# CPU.net
KiCad netlist of a schematic drawn in Altium Designer
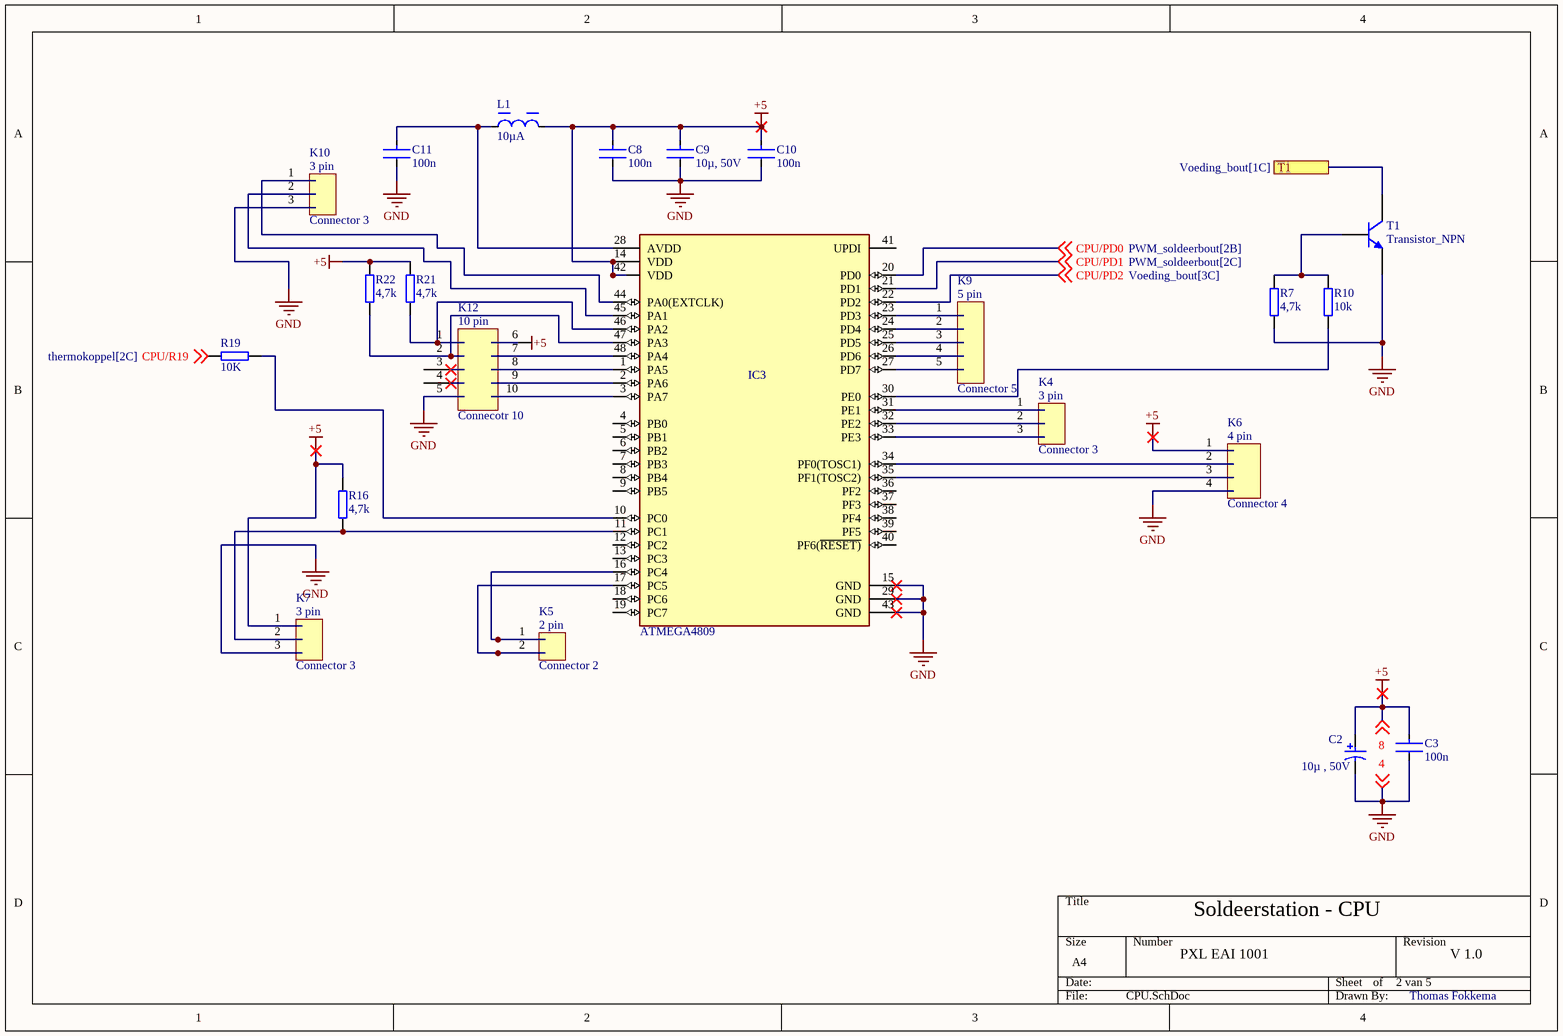
[diagram p0: CPU.SchDoc]

(export (version "E")
  (design (tool "Eeschema 10.0.6"))
  (components
    (comp (ref "C2")
      (value "10µ , 50V")
      (footprint "CE_D8_L10")
      (fields (field (name "MANUFACTURER") "Panasonic"))
      (libsource (lib "Schlib1") (part "Capacitor_Electrolytic"))
    )
    (comp (ref "C3")
      (value "100n")
      (footprint "CC_0805_L")
      (fields
        (field (name "MANUFACTURER") "KEMET")
        (field (name "OCTOPART") "https://octopart.com/c0805c224k5ractu-kemet-144670")
        (field (name "MANUFACTURER PART NUMBER") "C0805C224K5RACTU")
      )
      (libsource (lib "Schlib1") (part "Capacitor_Ceramic"))
    )
    (comp (ref "C8")
      (value "100n")
      (footprint "CC_0805_L")
      (fields
        (field (name "MANUFACTURER") "KEMET")
        (field (name "OCTOPART") "https://octopart.com/c0805c224k5ractu-kemet-144670")
        (field (name "MANUFACTURER PART NUMBER") "C0805C224K5RACTU")
      )
      (libsource (lib "Schlib1") (part "Capacitor_Ceramic"))
    )
    (comp (ref "C9")
      (value "10µ, 50V")
      (footprint "CC_0805_L")
      (fields
        (field (name "MANUFACTURER") "KEMET")
        (field (name "OCTOPART") "https://octopart.com/c0805c224k5ractu-kemet-144670")
        (field (name "MANUFACTURER PART NUMBER") "C0805C224K5RACTU")
      )
      (libsource (lib "Schlib1") (part "Capacitor_Ceramic"))
    )
    (comp (ref "C10")
      (value "100n")
      (footprint "CC_0805_L")
      (fields
        (field (name "MANUFACTURER") "KEMET")
        (field (name "OCTOPART") "https://octopart.com/c0805c224k5ractu-kemet-144670")
        (field (name "MANUFACTURER PART NUMBER") "C0805C224K5RACTU")
      )
      (libsource (lib "Schlib1") (part "Capacitor_Ceramic"))
    )
    (comp (ref "C11")
      (value "100n")
      (footprint "CC_0805_L")
      (fields
        (field (name "MANUFACTURER") "KEMET")
        (field (name "OCTOPART") "https://octopart.com/c0805c224k5ractu-kemet-144670")
        (field (name "MANUFACTURER PART NUMBER") "C0805C224K5RACTU")
      )
      (libsource (lib "Schlib1") (part "Capacitor_Ceramic"))
    )
    (comp (ref "IC3")
      (value "ATMEGA4809")
      (footprint "TQFP_48_M")
      (libsource (lib "Schlib1") (part "ATMEGA4809"))
    )
    (comp (ref "K4")
      (value "Connector 3")
      (footprint "HDR1X3")
      (libsource (lib "Soldeerstation_Final") (part "Connector 3"))
    )
    (comp (ref "K5")
      (value "Connector 2")
      (footprint "HDR1X2")
      (libsource (lib "Soldeerstation_Final") (part "Connector 2"))
    )
    (comp (ref "K6")
      (value "Connector 4")
      (footprint "HDR1X4")
      (libsource (lib "Soldeerstation_Final") (part "Connector 4"))
    )
    (comp (ref "K7")
      (value "Connector 3")
      (footprint "HDR1X3")
      (libsource (lib "Soldeerstation_Final") (part "Connector 3"))
    )
    (comp (ref "K9")
      (value "Connector 5")
      (footprint "HDR1X5")
      (libsource (lib "Soldeerstation_Final") (part "Connector 5"))
    )
    (comp (ref "K10")
      (value "Connector 3")
      (footprint "HDR1X3")
      (libsource (lib "Soldeerstation_Final") (part "Connector 3"))
    )
    (comp (ref "K12")
      (value "Connecotr 10")
      (footprint "HDR2X5")
      (libsource (lib "Soldeerstation_Final") (part "Connecotr 10"))
    )
    (comp (ref "L1")
      (value "10µA")
      (footprint "CC_0805_L")
      (fields (field (name "TOLERANCE") "20%"))
      (libsource (lib "Schlib1") (part "Choke"))
    )
    (comp (ref "R7")
      (value "4,7k")
      (footprint "R_0805_M")
      (fields (field (name "MANUFACTURER") "Vishay Dale") (field (name "PART NUMBER") "CRCW08050000Z0EA"))
      (libsource (lib "Schlib1") (part "Resistor"))
    )
    (comp (ref "R10")
      (value "10k")
      (footprint "R_0805_M")
      (fields (field (name "MANUFACTURER") "Vishay Dale") (field (name "PART NUMBER") "CRCW08050000Z0EA"))
      (libsource (lib "Schlib1") (part "Resistor"))
    )
    (comp (ref "R16")
      (value "4,7k")
      (footprint "R_0805_M")
      (fields (field (name "MANUFACTURER") "Vishay Dale") (field (name "PART NUMBER") "CRCW08050000Z0EA"))
      (libsource (lib "Schlib1") (part "Resistor"))
    )
    (comp (ref "R19")
      (value "10K")
      (footprint "R_0805_M")
      (fields (field (name "MANUFACTURER") "Vishay Dale") (field (name "PART NUMBER") "CRCW08050000Z0EA"))
      (libsource (lib "Schlib1") (part "Resistor"))
    )
    (comp (ref "R21")
      (value "4,7k")
      (footprint "R_0805_M")
      (fields (field (name "MANUFACTURER") "Vishay Dale") (field (name "PART NUMBER") "CRCW08050000Z0EA"))
      (libsource (lib "Schlib1") (part "Resistor"))
    )
    (comp (ref "R22")
      (value "4,7k")
      (footprint "R_0805_M")
      (fields (field (name "MANUFACTURER") "Vishay Dale") (field (name "PART NUMBER") "CRCW08050000Z0EA"))
      (libsource (lib "Schlib1") (part "Resistor"))
    )
    (comp (ref "T1")
      (value "Transistor_NPN")
      (footprint "SOT_23")
      (fields (field (name "MANUFACTURER") "On Semiconductor") (field (name "PARTNUMBER") "BC547C"))
      (libsource (lib "Schlib1") (part "Transistor_NPN"))
    )
  )
  (nets
    (net (code "1") (name "+5") (class "Default")
      (node (ref "C10") (pin "1") (pinfunction "1_1") (pintype "passive"))
      (node (ref "C2") (pin "2") (pinfunction "2_2") (pintype "passive"))
      (node (ref "C3") (pin "1") (pinfunction "1_1") (pintype "passive"))
      (node (ref "C8") (pin "1") (pinfunction "1_1") (pintype "passive"))
      (node (ref "C9") (pin "1") (pinfunction "1_1") (pintype "passive"))
      (node (ref "IC3") (pin "14") (pinfunction "VDD_14") (pintype "power_in"))
      (node (ref "IC3") (pin "42") (pinfunction "VDD_42") (pintype "power_in"))
      (node (ref "K12") (pin "6") (pinfunction "6_6") (pintype "passive"))
      (node (ref "K6") (pin "1") (pinfunction "24_1") (pintype "passive"))
      (node (ref "K7") (pin "1") (pinfunction "17_1") (pintype "passive"))
      (node (ref "L1") (pin "2") (pinfunction "2_2") (pintype "passive"))
      (node (ref "R16") (pin "2") (pinfunction "2_2") (pintype "passive"))
      (node (ref "R21") (pin "2") (pinfunction "2_2") (pintype "passive"))
      (node (ref "R22") (pin "2") (pinfunction "2_2") (pintype "passive"))
    )
    (net (code "2") (name "/T1") (class "Default")
      (node (ref "T1") (pin "1") (pinfunction "C_1") (pintype "passive"))
    )
    (net (code "3") (name "4") (class "Default")
      (node (ref "C10") (pin "2") (pinfunction "2_2") (pintype "passive"))
      (node (ref "C11") (pin "2") (pinfunction "2_2") (pintype "passive"))
      (node (ref "C2") (pin "1") (pinfunction "1_1") (pintype "passive"))
      (node (ref "C3") (pin "2") (pinfunction "2_2") (pintype "passive"))
      (node (ref "C8") (pin "2") (pinfunction "2_2") (pintype "passive"))
      (node (ref "C9") (pin "2") (pinfunction "2_2") (pintype "passive"))
      (node (ref "IC3") (pin "15") (pinfunction "GND_15") (pintype "open_emitter"))
      (node (ref "IC3") (pin "29") (pinfunction "GND_29") (pintype "power_in"))
      (node (ref "IC3") (pin "43") (pinfunction "GND_43") (pintype "power_in"))
      (node (ref "K10") (pin "3") (pinfunction "19_3") (pintype "passive"))
      (node (ref "K12") (pin "5") (pinfunction "32_5") (pintype "passive"))
      (node (ref "K6") (pin "4") (pinfunction "27_4") (pintype "passive"))
      (node (ref "K7") (pin "3") (pinfunction "19_3") (pintype "passive"))
      (node (ref "R7") (pin "1") (pinfunction "1_1") (pintype "passive"))
      (node (ref "T1") (pin "3") (pinfunction "E_3") (pintype "passive"))
    )
    (net (code "4") (name "CPU{slash}PD0") (class "Default")
      (node (ref "IC3") (pin "20") (pinfunction "PD0_20") (pintype "bidirectional"))
    )
    (net (code "5") (name "CPU{slash}PD1") (class "Default")
      (node (ref "IC3") (pin "21") (pinfunction "PD1_21") (pintype "bidirectional"))
    )
    (net (code "6") (name "CPU{slash}PD2") (class "Default")
      (node (ref "IC3") (pin "22") (pinfunction "PD2_22") (pintype "bidirectional"))
    )
    (net (code "7") (name "CPU{slash}R19") (class "Default")
      (node (ref "R19") (pin "1") (pinfunction "1_1") (pintype "passive"))
    )
    (net (code "8") (name "Net-(IC3-AVDD)") (class "Default")
      (node (ref "C11") (pin "1") (pinfunction "1_1") (pintype "passive"))
      (node (ref "IC3") (pin "28") (pinfunction "AVDD_28") (pintype "power_in"))
      (node (ref "L1") (pin "1") (pinfunction "1_1") (pintype "passive"))
    )
    (net (code "9") (name "Net-(IC3-PA0(EXTCLK))") (class "Default")
      (node (ref "IC3") (pin "44") (pinfunction "PA0(EXTCLK)_44") (pintype "bidirectional"))
      (node (ref "K10") (pin "1") (pinfunction "17_1") (pintype "passive"))
    )
    (net (code "10") (name "Net-(IC3-PA1)") (class "Default")
      (node (ref "IC3") (pin "45") (pinfunction "PA1_45") (pintype "bidirectional"))
      (node (ref "K10") (pin "2") (pinfunction "18_2") (pintype "passive"))
    )
    (net (code "11") (name "Net-(IC3-PA2)") (class "Default")
      (node (ref "IC3") (pin "46") (pinfunction "PA2_46") (pintype "bidirectional"))
      (node (ref "K12") (pin "1") (pinfunction "28_1") (pintype "passive"))
      (node (ref "R21") (pin "1") (pinfunction "1_1") (pintype "passive"))
    )
    (net (code "12") (name "Net-(IC3-PA3)") (class "Default")
      (node (ref "IC3") (pin "47") (pinfunction "PA3_47") (pintype "bidirectional"))
      (node (ref "K12") (pin "2") (pinfunction "29_2") (pintype "passive"))
      (node (ref "R22") (pin "1") (pinfunction "1_1") (pintype "passive"))
    )
    (net (code "13") (name "Net-(IC3-PA4)") (class "Default")
      (node (ref "IC3") (pin "48") (pinfunction "PA4_48") (pintype "bidirectional"))
      (node (ref "K12") (pin "7") (pinfunction "7_7") (pintype "passive"))
    )
    (net (code "14") (name "Net-(IC3-PA5)") (class "Default")
      (node (ref "IC3") (pin "1") (pinfunction "PA5_1") (pintype "bidirectional"))
      (node (ref "K12") (pin "8") (pinfunction "8_8") (pintype "passive"))
    )
    (net (code "15") (name "Net-(IC3-PA6)") (class "Default")
      (node (ref "IC3") (pin "2") (pinfunction "PA6_2") (pintype "bidirectional"))
      (node (ref "K12") (pin "9") (pinfunction "9_9") (pintype "passive"))
    )
    (net (code "16") (name "Net-(IC3-PA7)") (class "Default")
      (node (ref "IC3") (pin "3") (pinfunction "PA7_3") (pintype "bidirectional"))
      (node (ref "K12") (pin "10") (pinfunction "10_10") (pintype "passive"))
    )
    (net (code "17") (name "Net-(IC3-PC0)") (class "Default")
      (node (ref "IC3") (pin "10") (pinfunction "PC0_10") (pintype "bidirectional"))
      (node (ref "R19") (pin "2") (pinfunction "2_2") (pintype "passive"))
    )
    (net (code "18") (name "Net-(IC3-PC1)") (class "Default")
      (node (ref "IC3") (pin "11") (pinfunction "PC1_11") (pintype "bidirectional"))
      (node (ref "K7") (pin "2") (pinfunction "18_2") (pintype "passive"))
      (node (ref "R16") (pin "1") (pinfunction "1_1") (pintype "passive"))
    )
    (net (code "19") (name "Net-(IC3-PC4)") (class "Default")
      (node (ref "IC3") (pin "16") (pinfunction "PC4_16") (pintype "bidirectional"))
      (node (ref "K5") (pin "1") (pinfunction "15_1") (pintype "passive"))
    )
    (net (code "20") (name "Net-(IC3-PC5)") (class "Default")
      (node (ref "IC3") (pin "17") (pinfunction "PC5_17") (pintype "bidirectional"))
      (node (ref "K5") (pin "2") (pinfunction "16_2") (pintype "passive"))
    )
    (net (code "21") (name "Net-(IC3-PD3)") (class "Default")
      (node (ref "IC3") (pin "23") (pinfunction "PD3_23") (pintype "bidirectional"))
      (node (ref "K9") (pin "1") (pinfunction "28_1") (pintype "passive"))
    )
    (net (code "22") (name "Net-(IC3-PD4)") (class "Default")
      (node (ref "IC3") (pin "24") (pinfunction "PD4_24") (pintype "bidirectional"))
      (node (ref "K9") (pin "2") (pinfunction "29_2") (pintype "passive"))
    )
    (net (code "23") (name "Net-(IC3-PD5)") (class "Default")
      (node (ref "IC3") (pin "25") (pinfunction "PD5_25") (pintype "bidirectional"))
      (node (ref "K9") (pin "3") (pinfunction "30_3") (pintype "passive"))
    )
    (net (code "24") (name "Net-(IC3-PD6)") (class "Default")
      (node (ref "IC3") (pin "26") (pinfunction "PD6_26") (pintype "bidirectional"))
      (node (ref "K9") (pin "4") (pinfunction "31_4") (pintype "passive"))
    )
    (net (code "25") (name "Net-(IC3-PD7)") (class "Default")
      (node (ref "IC3") (pin "27") (pinfunction "PD7_27") (pintype "bidirectional"))
      (node (ref "K9") (pin "5") (pinfunction "32_5") (pintype "passive"))
    )
    (net (code "26") (name "Net-(IC3-PE0)") (class "Default")
      (node (ref "IC3") (pin "30") (pinfunction "PE0_30") (pintype "bidirectional"))
      (node (ref "R10") (pin "1") (pinfunction "1_1") (pintype "passive"))
    )
    (net (code "27") (name "Net-(IC3-PE1)") (class "Default")
      (node (ref "IC3") (pin "31") (pinfunction "PE1_31") (pintype "bidirectional"))
      (node (ref "K4") (pin "1") (pinfunction "17_1") (pintype "passive"))
    )
    (net (code "28") (name "Net-(IC3-PE2)") (class "Default")
      (node (ref "IC3") (pin "32") (pinfunction "PE2_32") (pintype "bidirectional"))
      (node (ref "K4") (pin "2") (pinfunction "18_2") (pintype "passive"))
    )
    (net (code "29") (name "Net-(IC3-PE3)") (class "Default")
      (node (ref "IC3") (pin "33") (pinfunction "PE3_33") (pintype "bidirectional"))
      (node (ref "K4") (pin "3") (pinfunction "19_3") (pintype "passive"))
    )
    (net (code "30") (name "Net-(IC3-PF0(TOSC1))") (class "Default")
      (node (ref "IC3") (pin "34") (pinfunction "PF0(TOSC1)_34") (pintype "bidirectional"))
      (node (ref "K6") (pin "2") (pinfunction "25_2") (pintype "passive"))
    )
    (net (code "31") (name "Net-(IC3-PF1(TOSC2))") (class "Default")
      (node (ref "IC3") (pin "35") (pinfunction "PF1(TOSC2)_35") (pintype "bidirectional"))
      (node (ref "K6") (pin "3") (pinfunction "26_3") (pintype "passive"))
    )
    (net (code "32") (name "Net-(T1-B)") (class "Default")
      (node (ref "R10") (pin "2") (pinfunction "2_2") (pintype "passive"))
      (node (ref "R7") (pin "2") (pinfunction "2_2") (pintype "passive"))
      (node (ref "T1") (pin "2") (pinfunction "B_2") (pintype "passive"))
    )
    (net (code "33") (name "unconnected-(IC3-PB0-Pad4)") (class "Default")
      (node (ref "IC3") (pin "4") (pinfunction "PB0_4") (pintype "bidirectional"))
    )
    (net (code "34") (name "unconnected-(IC3-PB1-Pad5)") (class "Default")
      (node (ref "IC3") (pin "5") (pinfunction "PB1_5") (pintype "bidirectional"))
    )
    (net (code "35") (name "unconnected-(IC3-PB2-Pad6)") (class "Default")
      (node (ref "IC3") (pin "6") (pinfunction "PB2_6") (pintype "bidirectional"))
    )
    (net (code "36") (name "unconnected-(IC3-PB3-Pad7)") (class "Default")
      (node (ref "IC3") (pin "7") (pinfunction "PB3_7") (pintype "bidirectional"))
    )
    (net (code "37") (name "unconnected-(IC3-PB4-Pad8)") (class "Default")
      (node (ref "IC3") (pin "8") (pinfunction "PB4_8") (pintype "bidirectional"))
    )
    (net (code "38") (name "unconnected-(IC3-PB5-Pad9)") (class "Default")
      (node (ref "IC3") (pin "9") (pinfunction "PB5_9") (pintype "bidirectional"))
    )
    (net (code "39") (name "unconnected-(IC3-PC2-Pad12)") (class "Default")
      (node (ref "IC3") (pin "12") (pinfunction "PC2_12") (pintype "bidirectional"))
    )
    (net (code "40") (name "unconnected-(IC3-PC3-Pad13)") (class "Default")
      (node (ref "IC3") (pin "13") (pinfunction "PC3_13") (pintype "bidirectional"))
    )
    (net (code "41") (name "unconnected-(IC3-PC6-Pad18)") (class "Default")
      (node (ref "IC3") (pin "18") (pinfunction "PC6_18") (pintype "bidirectional"))
    )
    (net (code "42") (name "unconnected-(IC3-PC7-Pad19)") (class "Default")
      (node (ref "IC3") (pin "19") (pinfunction "PC7_19") (pintype "bidirectional"))
    )
    (net (code "43") (name "unconnected-(IC3-PF2-Pad36)") (class "Default")
      (node (ref "IC3") (pin "36") (pinfunction "PF2_36") (pintype "bidirectional"))
    )
    (net (code "44") (name "unconnected-(IC3-PF3-Pad37)") (class "Default")
      (node (ref "IC3") (pin "37") (pinfunction "PF3_37") (pintype "bidirectional"))
    )
    (net (code "45") (name "unconnected-(IC3-PF4-Pad38)") (class "Default")
      (node (ref "IC3") (pin "38") (pinfunction "PF4_38") (pintype "bidirectional"))
    )
    (net (code "46") (name "unconnected-(IC3-PF5-Pad39)") (class "Default")
      (node (ref "IC3") (pin "39") (pinfunction "PF5_39") (pintype "bidirectional"))
    )
    (net (code "47") (name "unconnected-(IC3-PF6(~{RESET)}-Pad40)") (class "Default")
      (node (ref "IC3") (pin "40") (pinfunction "PF6(~{RESET)}_40") (pintype "bidirectional"))
    )
    (net (code "48") (name "unconnected-(IC3-UPDI-Pad41)") (class "Default")
      (node (ref "IC3") (pin "41") (pinfunction "UPDI_41") (pintype "passive"))
    )
    (net (code "49") (name "unconnected-(K12-30-Pad3)") (class "Default")
      (node (ref "K12") (pin "3") (pinfunction "30_3") (pintype "passive+no_connect"))
    )
    (net (code "50") (name "unconnected-(K12-31-Pad4)") (class "Default")
      (node (ref "K12") (pin "4") (pinfunction "31_4") (pintype "passive+no_connect"))
    )
  )
)
